# 20180608-iot.net
KiCad netlist of a schematic drawn in EAGLE
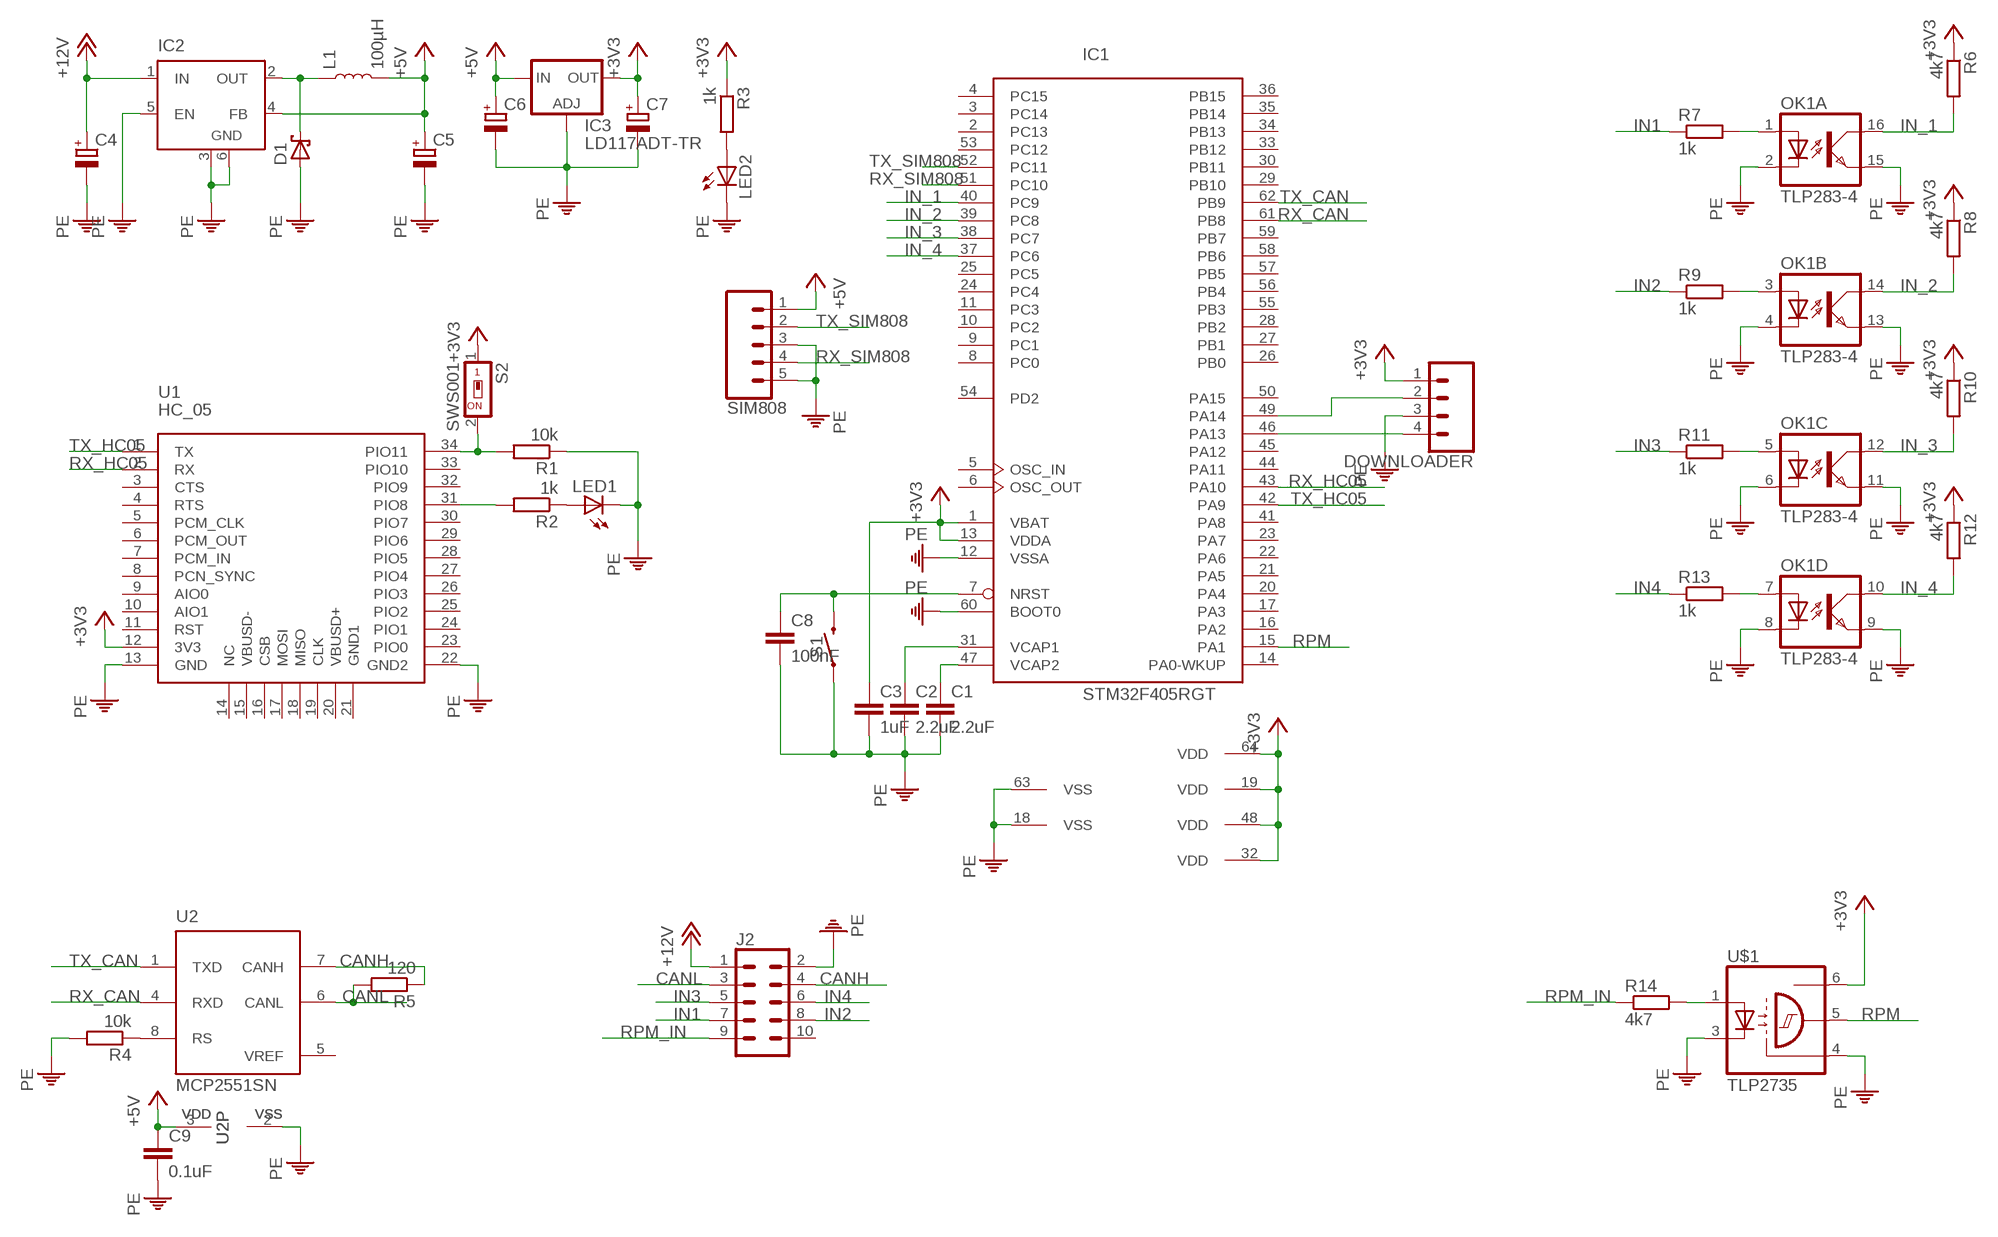
[diagram p0: schematic, sheet 1]

(export (version "E")
  (design (tool "Eeschema 10.0.6"))
  (components
    (comp (ref "C1")
      (value "2.2uF")
      (footprint "eagle-import:C0805")
      (libsource (lib "eagle-import") (part "C-EUC0805"))
    )
    (comp (ref "C2")
      (value "2.2uF")
      (footprint "eagle-import:C0805")
      (libsource (lib "eagle-import") (part "C-EUC0805"))
    )
    (comp (ref "C3")
      (value "1uF")
      (footprint "eagle-import:C0805")
      (libsource (lib "eagle-import") (part "C-EUC0805"))
    )
    (comp (ref "C4")
      (value "CPOL-EU153CLV-0605")
      (footprint "eagle-import:153CLV-0605")
      (libsource (lib "eagle-import") (part "CPOL-EU153CLV-0605"))
    )
    (comp (ref "C5")
      (value "CPOL-EU153CLV-0810")
      (footprint "eagle-import:153CLV-0810")
      (libsource (lib "eagle-import") (part "CPOL-EU153CLV-0810"))
    )
    (comp (ref "C6")
      (value "CPOL-EUCT7343")
      (footprint "eagle-import:CT7343")
      (libsource (lib "eagle-import") (part "CPOL-EUCT7343"))
    )
    (comp (ref "C7")
      (value "CPOL-EU153CLV-0605")
      (footprint "eagle-import:153CLV-0605")
      (libsource (lib "eagle-import") (part "CPOL-EU153CLV-0605"))
    )
    (comp (ref "C8")
      (value "100nF")
      (footprint "eagle-import:C0805")
      (libsource (lib "eagle-import") (part "C-EUC0805"))
    )
    (comp (ref "C9")
      (value "0.1uF")
      (footprint "eagle-import:C0805")
      (libsource (lib "eagle-import") (part "C-EUC0805"))
    )
    (comp (ref "D1")
      (value "SCHOTTKY-DIODESMD")
      (footprint "eagle-import:SMB")
      (libsource (lib "eagle-import") (part "SCHOTTKY-DIODESMD"))
    )
    (comp (ref "DOWNLOADER")
      (value "CONN_04")
      (footprint "eagle-import:1X04")
      (libsource (lib "eagle-import") (part "CONN_04"))
    )
    (comp (ref "IC1")
      (value "STM32F405RGT")
      (footprint "eagle-import:LQFP64")
      (fields (field (name "SPICEPREFIX") "X"))
      (libsource (lib "eagle-import") (part "STM32F405RTG"))
    )
    (comp (ref "IC2")
      (value "LM2596S")
      (footprint "eagle-import:TO263-5")
      (libsource (lib "eagle-import") (part "LM2596S"))
    )
    (comp (ref "IC3")
      (value "LD117ADT-TR")
      (footprint "eagle-import:DPACK")
      (libsource (lib "eagle-import") (part "LD117A?DT-TR"))
    )
    (comp (ref "J2")
      (value "CONN_05X2")
      (footprint "eagle-import:2X5-EDGE_SMD")
      (libsource (lib "eagle-import") (part "CONN_05X2"))
    )
    (comp (ref "L1")
      (value "100µH")
      (footprint "eagle-import:SRN6045")
      (libsource (lib "eagle-import") (part "INDUCTOR-SRN6045-33UH"))
    )
    (comp (ref "LED1")
      (value "LEDCHIP-LED0805")
      (footprint "eagle-import:CHIP-LED0805")
      (libsource (lib "eagle-import") (part "LEDCHIP-LED0805"))
    )
    (comp (ref "LED2")
      (value "LEDCHIP-LED0805")
      (footprint "eagle-import:CHIP-LED0805")
      (libsource (lib "eagle-import") (part "LEDCHIP-LED0805"))
    )
    (comp (ref "OK1")
      (value "TLP283-4")
      (footprint "eagle-import:MINI-FLAT-16")
      (libsource (lib "eagle-import") (part "TLP283-4"))
    )
    (comp (ref "R1")
      (value "10k")
      (footprint "eagle-import:R0805")
      (libsource (lib "eagle-import") (part "R-EU_R0805"))
    )
    (comp (ref "R2")
      (value "1k")
      (footprint "eagle-import:R0805")
      (libsource (lib "eagle-import") (part "R-EU_R0805"))
    )
    (comp (ref "R3")
      (value "1k")
      (footprint "eagle-import:R0805")
      (libsource (lib "eagle-import") (part "R-EU_R0805"))
    )
    (comp (ref "R4")
      (value "10k")
      (footprint "eagle-import:R0805")
      (libsource (lib "eagle-import") (part "R-EU_R0805"))
    )
    (comp (ref "R5")
      (value "120")
      (footprint "eagle-import:R0805")
      (libsource (lib "eagle-import") (part "R-EU_R0805"))
    )
    (comp (ref "R6")
      (value "4k7")
      (footprint "eagle-import:R0805")
      (libsource (lib "eagle-import") (part "R-EU_R0805"))
    )
    (comp (ref "R7")
      (value "1k")
      (footprint "eagle-import:R0805")
      (libsource (lib "eagle-import") (part "R-EU_R0805"))
    )
    (comp (ref "R8")
      (value "4k7")
      (footprint "eagle-import:R0805")
      (libsource (lib "eagle-import") (part "R-EU_R0805"))
    )
    (comp (ref "R9")
      (value "1k")
      (footprint "eagle-import:R0805")
      (libsource (lib "eagle-import") (part "R-EU_R0805"))
    )
    (comp (ref "R10")
      (value "4k7")
      (footprint "eagle-import:R0805")
      (libsource (lib "eagle-import") (part "R-EU_R0805"))
    )
    (comp (ref "R11")
      (value "1k")
      (footprint "eagle-import:R0805")
      (libsource (lib "eagle-import") (part "R-EU_R0805"))
    )
    (comp (ref "R12")
      (value "4k7")
      (footprint "eagle-import:R0805")
      (libsource (lib "eagle-import") (part "R-EU_R0805"))
    )
    (comp (ref "R13")
      (value "1k")
      (footprint "eagle-import:R0805")
      (libsource (lib "eagle-import") (part "R-EU_R0805"))
    )
    (comp (ref "R14")
      (value "4k7")
      (footprint "eagle-import:R0805")
      (libsource (lib "eagle-import") (part "R-EU_R0805"))
    )
    (comp (ref "S1")
      (value "MOMENTARY-SWITCH-SPST-SMD-6.0X3.5MM")
      (footprint "eagle-import:TACTILE_SWITCH_SMD_6.0X3.5MM")
      (libsource (lib "eagle-import") (part "MOMENTARY-SWITCH-SPST-SMD-6.0X3.5MM"))
    )
    (comp (ref "S2")
      (value "SWS001")
      (footprint "eagle-import:SMS-001")
      (libsource (lib "eagle-import") (part "SWS001"))
    )
    (comp (ref "SIM808")
      (value "CONN_05")
      (footprint "eagle-import:1X05")
      (libsource (lib "eagle-import") (part "CONN_05"))
    )
    (comp (ref "U$1")
      (value "TLP2735")
      (footprint "eagle-import:SOIC127P1000X210-6")
      (libsource (lib "eagle-import") (part "TLP2735"))
    )
    (comp (ref "U1")
      (value "HC_05")
      (footprint "eagle-import:BLUETOOTH_SMD")
      (libsource (lib "eagle-import") (part "HC_05"))
    )
    (comp (ref "U2")
      (value "MCP2551SN")
      (footprint "eagle-import:SO-08")
      (fields (field (name "SPICEPREFIX") "X"))
      (libsource (lib "eagle-import") (part "MCP2551SN"))
    )
  )
  (nets
    (net (code "1") (name "+3V3") (class "Default")
      (node (ref "C3") (pin "1") (pinfunction "1_1") (pintype "passive"))
      (node (ref "C7") (pin "+") (pinfunction "+_+") (pintype "passive"))
      (node (ref "DOWNLOADER") (pin "1") (pinfunction "1_1") (pintype "passive"))
      (node (ref "IC1") (pin "1") (pinfunction "VBAT_1") (pintype "power_in"))
      (node (ref "IC1") (pin "13") (pinfunction "VDDA_13") (pintype "power_in"))
      (node (ref "IC1") (pin "19") (pinfunction "VDD_19") (pintype "power_in"))
      (node (ref "IC1") (pin "32") (pinfunction "VDD_32") (pintype "power_in"))
      (node (ref "IC1") (pin "48") (pinfunction "VDD_48") (pintype "power_in"))
      (node (ref "IC1") (pin "64") (pinfunction "VDD_64") (pintype "power_in"))
      (node (ref "IC3") (pin "4") (pinfunction "OUT_4") (pintype "passive"))
      (node (ref "R10") (pin "1") (pinfunction "1_1") (pintype "passive"))
      (node (ref "R12") (pin "1") (pinfunction "1_1") (pintype "passive"))
      (node (ref "R3") (pin "1") (pinfunction "1_1") (pintype "passive"))
      (node (ref "R6") (pin "1") (pinfunction "1_1") (pintype "passive"))
      (node (ref "R8") (pin "1") (pinfunction "1_1") (pintype "passive"))
      (node (ref "S2") (pin "1") (pinfunction "1_1") (pintype "passive"))
      (node (ref "U$1") (pin "6") (pinfunction "VCC_6") (pintype "passive"))
      (node (ref "U1") (pin "12") (pinfunction "3V3_12") (pintype "bidirectional"))
    )
    (net (code "2") (name "+5V") (class "Default")
      (node (ref "C5") (pin "+") (pinfunction "+_+") (pintype "passive"))
      (node (ref "C6") (pin "+") (pinfunction "+_+") (pintype "passive"))
      (node (ref "C9") (pin "1") (pinfunction "1_1") (pintype "passive"))
      (node (ref "IC2") (pin "4") (pinfunction "FB_4") (pintype "input"))
      (node (ref "IC3") (pin "3") (pinfunction "IN_3") (pintype "input"))
      (node (ref "L1") (pin "2") (pinfunction "2_2") (pintype "passive"))
      (node (ref "SIM808") (pin "1") (pinfunction "1_1") (pintype "passive"))
      (node (ref "U2") (pin "3") (pinfunction "VDD_3") (pintype "power_in"))
    )
    (net (code "3") (name "+12V") (class "Default")
      (node (ref "C4") (pin "+") (pinfunction "+_+") (pintype "passive"))
      (node (ref "IC2") (pin "1") (pinfunction "IN_1") (pintype "input"))
      (node (ref "J2") (pin "1") (pinfunction "1_1") (pintype "passive"))
    )
    (net (code "4") (name "/CANH") (class "Default")
      (node (ref "J2") (pin "4") (pinfunction "4_4") (pintype "passive"))
      (node (ref "R5") (pin "1") (pinfunction "1_1") (pintype "passive"))
      (node (ref "U2") (pin "7") (pinfunction "CANH_7") (pintype "bidirectional"))
    )
    (net (code "5") (name "/CANL") (class "Default")
      (node (ref "J2") (pin "3") (pinfunction "3_3") (pintype "passive"))
      (node (ref "R5") (pin "2") (pinfunction "2_2") (pintype "passive"))
      (node (ref "U2") (pin "6") (pinfunction "CANL_6") (pintype "bidirectional"))
    )
    (net (code "6") (name "/IN1") (class "Default")
      (node (ref "J2") (pin "7") (pinfunction "7_7") (pintype "passive"))
      (node (ref "R7") (pin "1") (pinfunction "1_1") (pintype "passive"))
    )
    (net (code "7") (name "/IN2") (class "Default")
      (node (ref "J2") (pin "8") (pinfunction "8_8") (pintype "passive"))
      (node (ref "R9") (pin "1") (pinfunction "1_1") (pintype "passive"))
    )
    (net (code "8") (name "/IN3") (class "Default")
      (node (ref "J2") (pin "5") (pinfunction "5_5") (pintype "passive"))
      (node (ref "R11") (pin "1") (pinfunction "1_1") (pintype "passive"))
    )
    (net (code "9") (name "/IN4") (class "Default")
      (node (ref "J2") (pin "6") (pinfunction "6_6") (pintype "passive"))
      (node (ref "R13") (pin "1") (pinfunction "1_1") (pintype "passive"))
    )
    (net (code "10") (name "/IN_1") (class "Default")
      (node (ref "IC1") (pin "40") (pinfunction "PC9_40") (pintype "bidirectional"))
      (node (ref "OK1") (pin "16") (pinfunction "COL_16") (pintype "passive"))
      (node (ref "R6") (pin "2") (pinfunction "2_2") (pintype "passive"))
    )
    (net (code "11") (name "/IN_2") (class "Default")
      (node (ref "IC1") (pin "39") (pinfunction "PC8_39") (pintype "bidirectional"))
      (node (ref "OK1") (pin "14") (pinfunction "COL_14") (pintype "passive"))
      (node (ref "R8") (pin "2") (pinfunction "2_2") (pintype "passive"))
    )
    (net (code "12") (name "/IN_3") (class "Default")
      (node (ref "IC1") (pin "38") (pinfunction "PC7_38") (pintype "bidirectional"))
      (node (ref "OK1") (pin "12") (pinfunction "COL_12") (pintype "passive"))
      (node (ref "R10") (pin "2") (pinfunction "2_2") (pintype "passive"))
    )
    (net (code "13") (name "/IN_4") (class "Default")
      (node (ref "IC1") (pin "37") (pinfunction "PC6_37") (pintype "bidirectional"))
      (node (ref "OK1") (pin "10") (pinfunction "COL_10") (pintype "passive"))
      (node (ref "R12") (pin "2") (pinfunction "2_2") (pintype "passive"))
    )
    (net (code "14") (name "/RPM") (class "Default")
      (node (ref "IC1") (pin "15") (pinfunction "PA1_15") (pintype "bidirectional"))
      (node (ref "U$1") (pin "5") (pinfunction "OUT_5") (pintype "passive"))
    )
    (net (code "15") (name "/RPM_IN") (class "Default")
      (node (ref "J2") (pin "9") (pinfunction "9_9") (pintype "passive"))
      (node (ref "R14") (pin "1") (pinfunction "1_1") (pintype "passive"))
    )
    (net (code "16") (name "/RX_CAN") (class "Default")
      (node (ref "IC1") (pin "61") (pinfunction "PB8_61") (pintype "bidirectional"))
      (node (ref "U2") (pin "4") (pinfunction "RXD_4") (pintype "output"))
    )
    (net (code "17") (name "/RX_HC05") (class "Default")
      (node (ref "IC1") (pin "43") (pinfunction "PA10_43") (pintype "bidirectional"))
      (node (ref "U1") (pin "2") (pinfunction "RX_2") (pintype "bidirectional"))
    )
    (net (code "18") (name "/RX_SIM808") (class "Default")
      (node (ref "IC1") (pin "51") (pinfunction "PC10_51") (pintype "bidirectional"))
      (node (ref "SIM808") (pin "4") (pinfunction "4_4") (pintype "passive"))
    )
    (net (code "19") (name "/TX_CAN") (class "Default")
      (node (ref "IC1") (pin "62") (pinfunction "PB9_62") (pintype "bidirectional"))
      (node (ref "U2") (pin "1") (pinfunction "TXD_1") (pintype "input"))
    )
    (net (code "20") (name "/TX_HC05") (class "Default")
      (node (ref "IC1") (pin "42") (pinfunction "PA9_42") (pintype "bidirectional"))
      (node (ref "U1") (pin "1") (pinfunction "TX_1") (pintype "bidirectional"))
    )
    (net (code "21") (name "/TX_SIM808") (class "Default")
      (node (ref "IC1") (pin "52") (pinfunction "PC11_52") (pintype "bidirectional"))
      (node (ref "SIM808") (pin "2") (pinfunction "2_2") (pintype "passive"))
    )
    (net (code "22") (name "/VREF") (class "Default")
      (node (ref "U2") (pin "5") (pinfunction "VREF_5") (pintype "power_in"))
    )
    (net (code "23") (name "Net-(IC1A-NRST)") (class "Default")
      (node (ref "C8") (pin "1") (pinfunction "1_1") (pintype "passive"))
      (node (ref "IC1") (pin "7") (pinfunction "NRST_7") (pintype "bidirectional"))
      (node (ref "S1") (pin "2") (pinfunction "2_2") (pintype "passive"))
    )
    (net (code "24") (name "Net-(IC1A-PA13)") (class "Default")
      (node (ref "DOWNLOADER") (pin "4") (pinfunction "4_4") (pintype "passive"))
      (node (ref "IC1") (pin "46") (pinfunction "PA13_46") (pintype "bidirectional"))
    )
    (net (code "25") (name "Net-(IC1A-PA14)") (class "Default")
      (node (ref "DOWNLOADER") (pin "2") (pinfunction "2_2") (pintype "passive"))
      (node (ref "IC1") (pin "49") (pinfunction "PA14_49") (pintype "bidirectional"))
    )
    (net (code "26") (name "Net-(IC1A-VCAP1)") (class "Default")
      (node (ref "C2") (pin "1") (pinfunction "1_1") (pintype "passive"))
      (node (ref "IC1") (pin "31") (pinfunction "VCAP1_31") (pintype "power_in"))
    )
    (net (code "27") (name "Net-(IC1A-VCAP2)") (class "Default")
      (node (ref "C1") (pin "1") (pinfunction "1_1") (pintype "passive"))
      (node (ref "IC1") (pin "47") (pinfunction "VCAP2_47") (pintype "power_in"))
    )
    (net (code "28") (name "Net-(IC2-OUT)") (class "Default")
      (node (ref "D1") (pin "C") (pinfunction "C_C") (pintype "passive"))
      (node (ref "IC2") (pin "2") (pinfunction "OUT_2") (pintype "output"))
      (node (ref "L1") (pin "1") (pinfunction "1_1") (pintype "passive"))
    )
    (net (code "29") (name "Net-(LED1-PadA)") (class "Default")
      (node (ref "LED1") (pin "A") (pinfunction "A_A") (pintype "passive"))
      (node (ref "R2") (pin "1") (pinfunction "1_1") (pintype "passive"))
    )
    (net (code "30") (name "Net-(LED2-PadA)") (class "Default")
      (node (ref "LED2") (pin "A") (pinfunction "A_A") (pintype "passive"))
      (node (ref "R3") (pin "2") (pinfunction "2_2") (pintype "passive"))
    )
    (net (code "31") (name "Net-(OK1A-A)") (class "Default")
      (node (ref "OK1") (pin "1") (pinfunction "A_1") (pintype "passive"))
      (node (ref "R7") (pin "2") (pinfunction "2_2") (pintype "passive"))
    )
    (net (code "32") (name "Net-(OK1B-A)") (class "Default")
      (node (ref "OK1") (pin "3") (pinfunction "A_3") (pintype "passive"))
      (node (ref "R9") (pin "2") (pinfunction "2_2") (pintype "passive"))
    )
    (net (code "33") (name "Net-(OK1C-A)") (class "Default")
      (node (ref "OK1") (pin "5") (pinfunction "A_5") (pintype "passive"))
      (node (ref "R11") (pin "2") (pinfunction "2_2") (pintype "passive"))
    )
    (net (code "34") (name "Net-(OK1D-A)") (class "Default")
      (node (ref "OK1") (pin "7") (pinfunction "A_7") (pintype "passive"))
      (node (ref "R13") (pin "2") (pinfunction "2_2") (pintype "passive"))
    )
    (net (code "35") (name "Net-(U$1-A)") (class "Default")
      (node (ref "R14") (pin "2") (pinfunction "2_2") (pintype "passive"))
      (node (ref "U$1") (pin "1") (pinfunction "A_1") (pintype "passive"))
    )
    (net (code "36") (name "Net-(U1-PIO8)") (class "Default")
      (node (ref "R2") (pin "2") (pinfunction "2_2") (pintype "passive"))
      (node (ref "U1") (pin "31") (pinfunction "PIO8_31") (pintype "bidirectional"))
    )
    (net (code "37") (name "Net-(U1-PIO11)") (class "Default")
      (node (ref "R1") (pin "2") (pinfunction "2_2") (pintype "passive"))
      (node (ref "S2") (pin "2") (pinfunction "2_2") (pintype "passive"))
      (node (ref "U1") (pin "34") (pinfunction "PIO11_34") (pintype "bidirectional"))
    )
    (net (code "38") (name "Net-(U2A-RS)") (class "Default")
      (node (ref "R4") (pin "1") (pinfunction "1_1") (pintype "passive"))
      (node (ref "U2") (pin "8") (pinfunction "RS_8") (pintype "input"))
    )
    (net (code "39") (name "PE") (class "Default")
      (node (ref "C1") (pin "2") (pinfunction "2_2") (pintype "passive"))
      (node (ref "C2") (pin "2") (pinfunction "2_2") (pintype "passive"))
      (node (ref "C3") (pin "2") (pinfunction "2_2") (pintype "passive"))
      (node (ref "C4") (pin "-") (pinfunction "-_-") (pintype "passive"))
      (node (ref "C5") (pin "-") (pinfunction "-_-") (pintype "passive"))
      (node (ref "C6") (pin "-") (pinfunction "-_-") (pintype "passive"))
      (node (ref "C7") (pin "-") (pinfunction "-_-") (pintype "passive"))
      (node (ref "C8") (pin "2") (pinfunction "2_2") (pintype "passive"))
      (node (ref "C9") (pin "2") (pinfunction "2_2") (pintype "passive"))
      (node (ref "D1") (pin "A") (pinfunction "A_A") (pintype "passive"))
      (node (ref "DOWNLOADER") (pin "3") (pinfunction "3_3") (pintype "passive"))
      (node (ref "IC1") (pin "12") (pinfunction "VSSA_12") (pintype "power_in"))
      (node (ref "IC1") (pin "18") (pinfunction "VSS_18") (pintype "power_in"))
      (node (ref "IC1") (pin "60") (pinfunction "BOOT0_60") (pintype "input"))
      (node (ref "IC1") (pin "63") (pinfunction "VSS_63") (pintype "power_in"))
      (node (ref "IC2") (pin "3") (pinfunction "GND_3") (pintype "power_in"))
      (node (ref "IC2") (pin "5") (pinfunction "EN_5") (pintype "input"))
      (node (ref "IC2") (pin "6") (pinfunction "GND_6") (pintype "power_in"))
      (node (ref "IC3") (pin "1") (pinfunction "ADJ_1") (pintype "input"))
      (node (ref "J2") (pin "2") (pinfunction "2_2") (pintype "passive"))
      (node (ref "LED1") (pin "C") (pinfunction "C_C") (pintype "passive"))
      (node (ref "LED2") (pin "C") (pinfunction "C_C") (pintype "passive"))
      (node (ref "OK1") (pin "11") (pinfunction "EMIT_11") (pintype "passive"))
      (node (ref "OK1") (pin "13") (pinfunction "EMIT_13") (pintype "passive"))
      (node (ref "OK1") (pin "15") (pinfunction "EMIT_15") (pintype "passive"))
      (node (ref "OK1") (pin "2") (pinfunction "C_2") (pintype "passive"))
      (node (ref "OK1") (pin "4") (pinfunction "C_4") (pintype "passive"))
      (node (ref "OK1") (pin "6") (pinfunction "C_6") (pintype "passive"))
      (node (ref "OK1") (pin "8") (pinfunction "C_8") (pintype "passive"))
      (node (ref "OK1") (pin "9") (pinfunction "EMIT_9") (pintype "passive"))
      (node (ref "R1") (pin "1") (pinfunction "1_1") (pintype "passive"))
      (node (ref "R4") (pin "2") (pinfunction "2_2") (pintype "passive"))
      (node (ref "S1") (pin "1") (pinfunction "1_1") (pintype "passive"))
      (node (ref "SIM808") (pin "3") (pinfunction "3_3") (pintype "passive"))
      (node (ref "SIM808") (pin "5") (pinfunction "5_5") (pintype "passive"))
      (node (ref "U$1") (pin "3") (pinfunction "C_3") (pintype "passive"))
      (node (ref "U$1") (pin "4") (pinfunction "GND_4") (pintype "passive"))
      (node (ref "U1") (pin "13") (pinfunction "GND_13") (pintype "bidirectional"))
      (node (ref "U1") (pin "22") (pinfunction "GND2_22") (pintype "bidirectional"))
      (node (ref "U2") (pin "2") (pinfunction "VSS_2") (pintype "power_in"))
    )
    (net (code "40") (name "unconnected-(IC1A-OSC_IN-Pad5)") (class "Default")
      (node (ref "IC1") (pin "5") (pinfunction "OSC_IN_5") (pintype "bidirectional"))
    )
    (net (code "41") (name "unconnected-(IC1A-OSC_OUT-Pad6)") (class "Default")
      (node (ref "IC1") (pin "6") (pinfunction "OSC_OUT_6") (pintype "bidirectional"))
    )
    (net (code "42") (name "unconnected-(IC1A-PA0-WKUP-Pad14)") (class "Default")
      (node (ref "IC1") (pin "14") (pinfunction "PA0-WKUP_14") (pintype "bidirectional"))
    )
    (net (code "43") (name "unconnected-(IC1A-PA2-Pad16)") (class "Default")
      (node (ref "IC1") (pin "16") (pinfunction "PA2_16") (pintype "bidirectional"))
    )
    (net (code "44") (name "unconnected-(IC1A-PA3-Pad17)") (class "Default")
      (node (ref "IC1") (pin "17") (pinfunction "PA3_17") (pintype "bidirectional"))
    )
    (net (code "45") (name "unconnected-(IC1A-PA4-Pad20)") (class "Default")
      (node (ref "IC1") (pin "20") (pinfunction "PA4_20") (pintype "bidirectional"))
    )
    (net (code "46") (name "unconnected-(IC1A-PA5-Pad21)") (class "Default")
      (node (ref "IC1") (pin "21") (pinfunction "PA5_21") (pintype "bidirectional"))
    )
    (net (code "47") (name "unconnected-(IC1A-PA6-Pad22)") (class "Default")
      (node (ref "IC1") (pin "22") (pinfunction "PA6_22") (pintype "bidirectional"))
    )
    (net (code "48") (name "unconnected-(IC1A-PA7-Pad23)") (class "Default")
      (node (ref "IC1") (pin "23") (pinfunction "PA7_23") (pintype "bidirectional"))
    )
    (net (code "49") (name "unconnected-(IC1A-PA8-Pad41)") (class "Default")
      (node (ref "IC1") (pin "41") (pinfunction "PA8_41") (pintype "bidirectional"))
    )
    (net (code "50") (name "unconnected-(IC1A-PA11-Pad44)") (class "Default")
      (node (ref "IC1") (pin "44") (pinfunction "PA11_44") (pintype "bidirectional"))
    )
    (net (code "51") (name "unconnected-(IC1A-PA12-Pad45)") (class "Default")
      (node (ref "IC1") (pin "45") (pinfunction "PA12_45") (pintype "bidirectional"))
    )
    (net (code "52") (name "unconnected-(IC1A-PA15-Pad50)") (class "Default")
      (node (ref "IC1") (pin "50") (pinfunction "PA15_50") (pintype "bidirectional"))
    )
    (net (code "53") (name "unconnected-(IC1A-PB0-Pad26)") (class "Default")
      (node (ref "IC1") (pin "26") (pinfunction "PB0_26") (pintype "bidirectional"))
    )
    (net (code "54") (name "unconnected-(IC1A-PB1-Pad27)") (class "Default")
      (node (ref "IC1") (pin "27") (pinfunction "PB1_27") (pintype "bidirectional"))
    )
    (net (code "55") (name "unconnected-(IC1A-PB2-Pad28)") (class "Default")
      (node (ref "IC1") (pin "28") (pinfunction "PB2_28") (pintype "bidirectional"))
    )
    (net (code "56") (name "unconnected-(IC1A-PB3-Pad55)") (class "Default")
      (node (ref "IC1") (pin "55") (pinfunction "PB3_55") (pintype "bidirectional"))
    )
    (net (code "57") (name "unconnected-(IC1A-PB4-Pad56)") (class "Default")
      (node (ref "IC1") (pin "56") (pinfunction "PB4_56") (pintype "bidirectional"))
    )
    (net (code "58") (name "unconnected-(IC1A-PB5-Pad57)") (class "Default")
      (node (ref "IC1") (pin "57") (pinfunction "PB5_57") (pintype "bidirectional"))
    )
    (net (code "59") (name "unconnected-(IC1A-PB6-Pad58)") (class "Default")
      (node (ref "IC1") (pin "58") (pinfunction "PB6_58") (pintype "bidirectional"))
    )
    (net (code "60") (name "unconnected-(IC1A-PB7-Pad59)") (class "Default")
      (node (ref "IC1") (pin "59") (pinfunction "PB7_59") (pintype "bidirectional"))
    )
    (net (code "61") (name "unconnected-(IC1A-PB10-Pad29)") (class "Default")
      (node (ref "IC1") (pin "29") (pinfunction "PB10_29") (pintype "bidirectional"))
    )
    (net (code "62") (name "unconnected-(IC1A-PB11-Pad30)") (class "Default")
      (node (ref "IC1") (pin "30") (pinfunction "PB11_30") (pintype "bidirectional"))
    )
    (net (code "63") (name "unconnected-(IC1A-PB12-Pad33)") (class "Default")
      (node (ref "IC1") (pin "33") (pinfunction "PB12_33") (pintype "bidirectional"))
    )
    (net (code "64") (name "unconnected-(IC1A-PB13-Pad34)") (class "Default")
      (node (ref "IC1") (pin "34") (pinfunction "PB13_34") (pintype "bidirectional"))
    )
    (net (code "65") (name "unconnected-(IC1A-PB14-Pad35)") (class "Default")
      (node (ref "IC1") (pin "35") (pinfunction "PB14_35") (pintype "bidirectional"))
    )
    (net (code "66") (name "unconnected-(IC1A-PB15-Pad36)") (class "Default")
      (node (ref "IC1") (pin "36") (pinfunction "PB15_36") (pintype "bidirectional"))
    )
    (net (code "67") (name "unconnected-(IC1A-PC0-Pad8)") (class "Default")
      (node (ref "IC1") (pin "8") (pinfunction "PC0_8") (pintype "bidirectional"))
    )
    (net (code "68") (name "unconnected-(IC1A-PC1-Pad9)") (class "Default")
      (node (ref "IC1") (pin "9") (pinfunction "PC1_9") (pintype "bidirectional"))
    )
    (net (code "69") (name "unconnected-(IC1A-PC2-Pad10)") (class "Default")
      (node (ref "IC1") (pin "10") (pinfunction "PC2_10") (pintype "bidirectional"))
    )
    (net (code "70") (name "unconnected-(IC1A-PC3-Pad11)") (class "Default")
      (node (ref "IC1") (pin "11") (pinfunction "PC3_11") (pintype "bidirectional"))
    )
    (net (code "71") (name "unconnected-(IC1A-PC4-Pad24)") (class "Default")
      (node (ref "IC1") (pin "24") (pinfunction "PC4_24") (pintype "bidirectional"))
    )
    (net (code "72") (name "unconnected-(IC1A-PC5-Pad25)") (class "Default")
      (node (ref "IC1") (pin "25") (pinfunction "PC5_25") (pintype "bidirectional"))
    )
    (net (code "73") (name "unconnected-(IC1A-PC12-Pad53)") (class "Default")
      (node (ref "IC1") (pin "53") (pinfunction "PC12_53") (pintype "bidirectional"))
    )
    (net (code "74") (name "unconnected-(IC1A-PC13-Pad2)") (class "Default")
      (node (ref "IC1") (pin "2") (pinfunction "PC13_2") (pintype "bidirectional"))
    )
    (net (code "75") (name "unconnected-(IC1A-PC14-Pad3)") (class "Default")
      (node (ref "IC1") (pin "3") (pinfunction "PC14_3") (pintype "bidirectional"))
    )
    (net (code "76") (name "unconnected-(IC1A-PC15-Pad4)") (class "Default")
      (node (ref "IC1") (pin "4") (pinfunction "PC15_4") (pintype "bidirectional"))
    )
    (net (code "77") (name "unconnected-(IC1A-PD2-Pad54)") (class "Default")
      (node (ref "IC1") (pin "54") (pinfunction "PD2_54") (pintype "bidirectional"))
    )
    (net (code "78") (name "unconnected-(J2-Pad10)") (class "Default")
      (node (ref "J2") (pin "10") (pinfunction "10_10") (pintype "passive"))
    )
    (net (code "79") (name "unconnected-(U1-AIO0-Pad9)") (class "Default")
      (node (ref "U1") (pin "9") (pinfunction "AIO0_9") (pintype "bidirectional"))
    )
    (net (code "80") (name "unconnected-(U1-AIO1-Pad10)") (class "Default")
      (node (ref "U1") (pin "10") (pinfunction "AIO1_10") (pintype "bidirectional"))
    )
    (net (code "81") (name "unconnected-(U1-CLK-Pad19)") (class "Default")
      (node (ref "U1") (pin "19") (pinfunction "CLK_19") (pintype "bidirectional"))
    )
    (net (code "82") (name "unconnected-(U1-CSB-Pad16)") (class "Default")
      (node (ref "U1") (pin "16") (pinfunction "CSB_16") (pintype "bidirectional"))
    )
    (net (code "83") (name "unconnected-(U1-CTS-Pad3)") (class "Default")
      (node (ref "U1") (pin "3") (pinfunction "CTS_3") (pintype "bidirectional"))
    )
    (net (code "84") (name "unconnected-(U1-GND1-Pad21)") (class "Default")
      (node (ref "U1") (pin "21") (pinfunction "GND1_21") (pintype "bidirectional"))
    )
    (net (code "85") (name "unconnected-(U1-MISO-Pad18)") (class "Default")
      (node (ref "U1") (pin "18") (pinfunction "MISO_18") (pintype "bidirectional"))
    )
    (net (code "86") (name "unconnected-(U1-MOSI-Pad17)") (class "Default")
      (node (ref "U1") (pin "17") (pinfunction "MOSI_17") (pintype "bidirectional"))
    )
    (net (code "87") (name "unconnected-(U1-NC-Pad14)") (class "Default")
      (node (ref "U1") (pin "14") (pinfunction "NC_14") (pintype "bidirectional"))
    )
    (net (code "88") (name "unconnected-(U1-PCM_CLK-Pad5)") (class "Default")
      (node (ref "U1") (pin "5") (pinfunction "PCM_CLK_5") (pintype "bidirectional"))
    )
    (net (code "89") (name "unconnected-(U1-PCM_IN-Pad7)") (class "Default")
      (node (ref "U1") (pin "7") (pinfunction "PCM_IN_7") (pintype "bidirectional"))
    )
    (net (code "90") (name "unconnected-(U1-PCM_OUT-Pad6)") (class "Default")
      (node (ref "U1") (pin "6") (pinfunction "PCM_OUT_6") (pintype "bidirectional"))
    )
    (net (code "91") (name "unconnected-(U1-PCN_SYNC-Pad8)") (class "Default")
      (node (ref "U1") (pin "8") (pinfunction "PCN_SYNC_8") (pintype "bidirectional"))
    )
    (net (code "92") (name "unconnected-(U1-PIO0-Pad23)") (class "Default")
      (node (ref "U1") (pin "23") (pinfunction "PIO0_23") (pintype "bidirectional"))
    )
    (net (code "93") (name "unconnected-(U1-PIO1-Pad24)") (class "Default")
      (node (ref "U1") (pin "24") (pinfunction "PIO1_24") (pintype "bidirectional"))
    )
    (net (code "94") (name "unconnected-(U1-PIO2-Pad25)") (class "Default")
      (node (ref "U1") (pin "25") (pinfunction "PIO2_25") (pintype "bidirectional"))
    )
    (net (code "95") (name "unconnected-(U1-PIO3-Pad26)") (class "Default")
      (node (ref "U1") (pin "26") (pinfunction "PIO3_26") (pintype "bidirectional"))
    )
    (net (code "96") (name "unconnected-(U1-PIO4-Pad27)") (class "Default")
      (node (ref "U1") (pin "27") (pinfunction "PIO4_27") (pintype "bidirectional"))
    )
    (net (code "97") (name "unconnected-(U1-PIO5-Pad28)") (class "Default")
      (node (ref "U1") (pin "28") (pinfunction "PIO5_28") (pintype "bidirectional"))
    )
    (net (code "98") (name "unconnected-(U1-PIO6-Pad29)") (class "Default")
      (node (ref "U1") (pin "29") (pinfunction "PIO6_29") (pintype "bidirectional"))
    )
    (net (code "99") (name "unconnected-(U1-PIO7-Pad30)") (class "Default")
      (node (ref "U1") (pin "30") (pinfunction "PIO7_30") (pintype "bidirectional"))
    )
    (net (code "100") (name "unconnected-(U1-PIO9-Pad32)") (class "Default")
      (node (ref "U1") (pin "32") (pinfunction "PIO9_32") (pintype "bidirectional"))
    )
    (net (code "101") (name "unconnected-(U1-PIO10-Pad33)") (class "Default")
      (node (ref "U1") (pin "33") (pinfunction "PIO10_33") (pintype "bidirectional"))
    )
    (net (code "102") (name "unconnected-(U1-RST-Pad11)") (class "Default")
      (node (ref "U1") (pin "11") (pinfunction "RST_11") (pintype "bidirectional"))
    )
    (net (code "103") (name "unconnected-(U1-RTS-Pad4)") (class "Default")
      (node (ref "U1") (pin "4") (pinfunction "RTS_4") (pintype "bidirectional"))
    )
    (net (code "104") (name "unconnected-(U1-VBUSD+-Pad20)") (class "Default")
      (node (ref "U1") (pin "20") (pinfunction "VBUSD+_20") (pintype "bidirectional"))
    )
    (net (code "105") (name "unconnected-(U1-VBUSD--Pad15)") (class "Default")
      (node (ref "U1") (pin "15") (pinfunction "VBUSD-_15") (pintype "bidirectional"))
    )
  )
)
